# V-00716-02.net
KiCad netlist of a schematic drawn in EAGLE
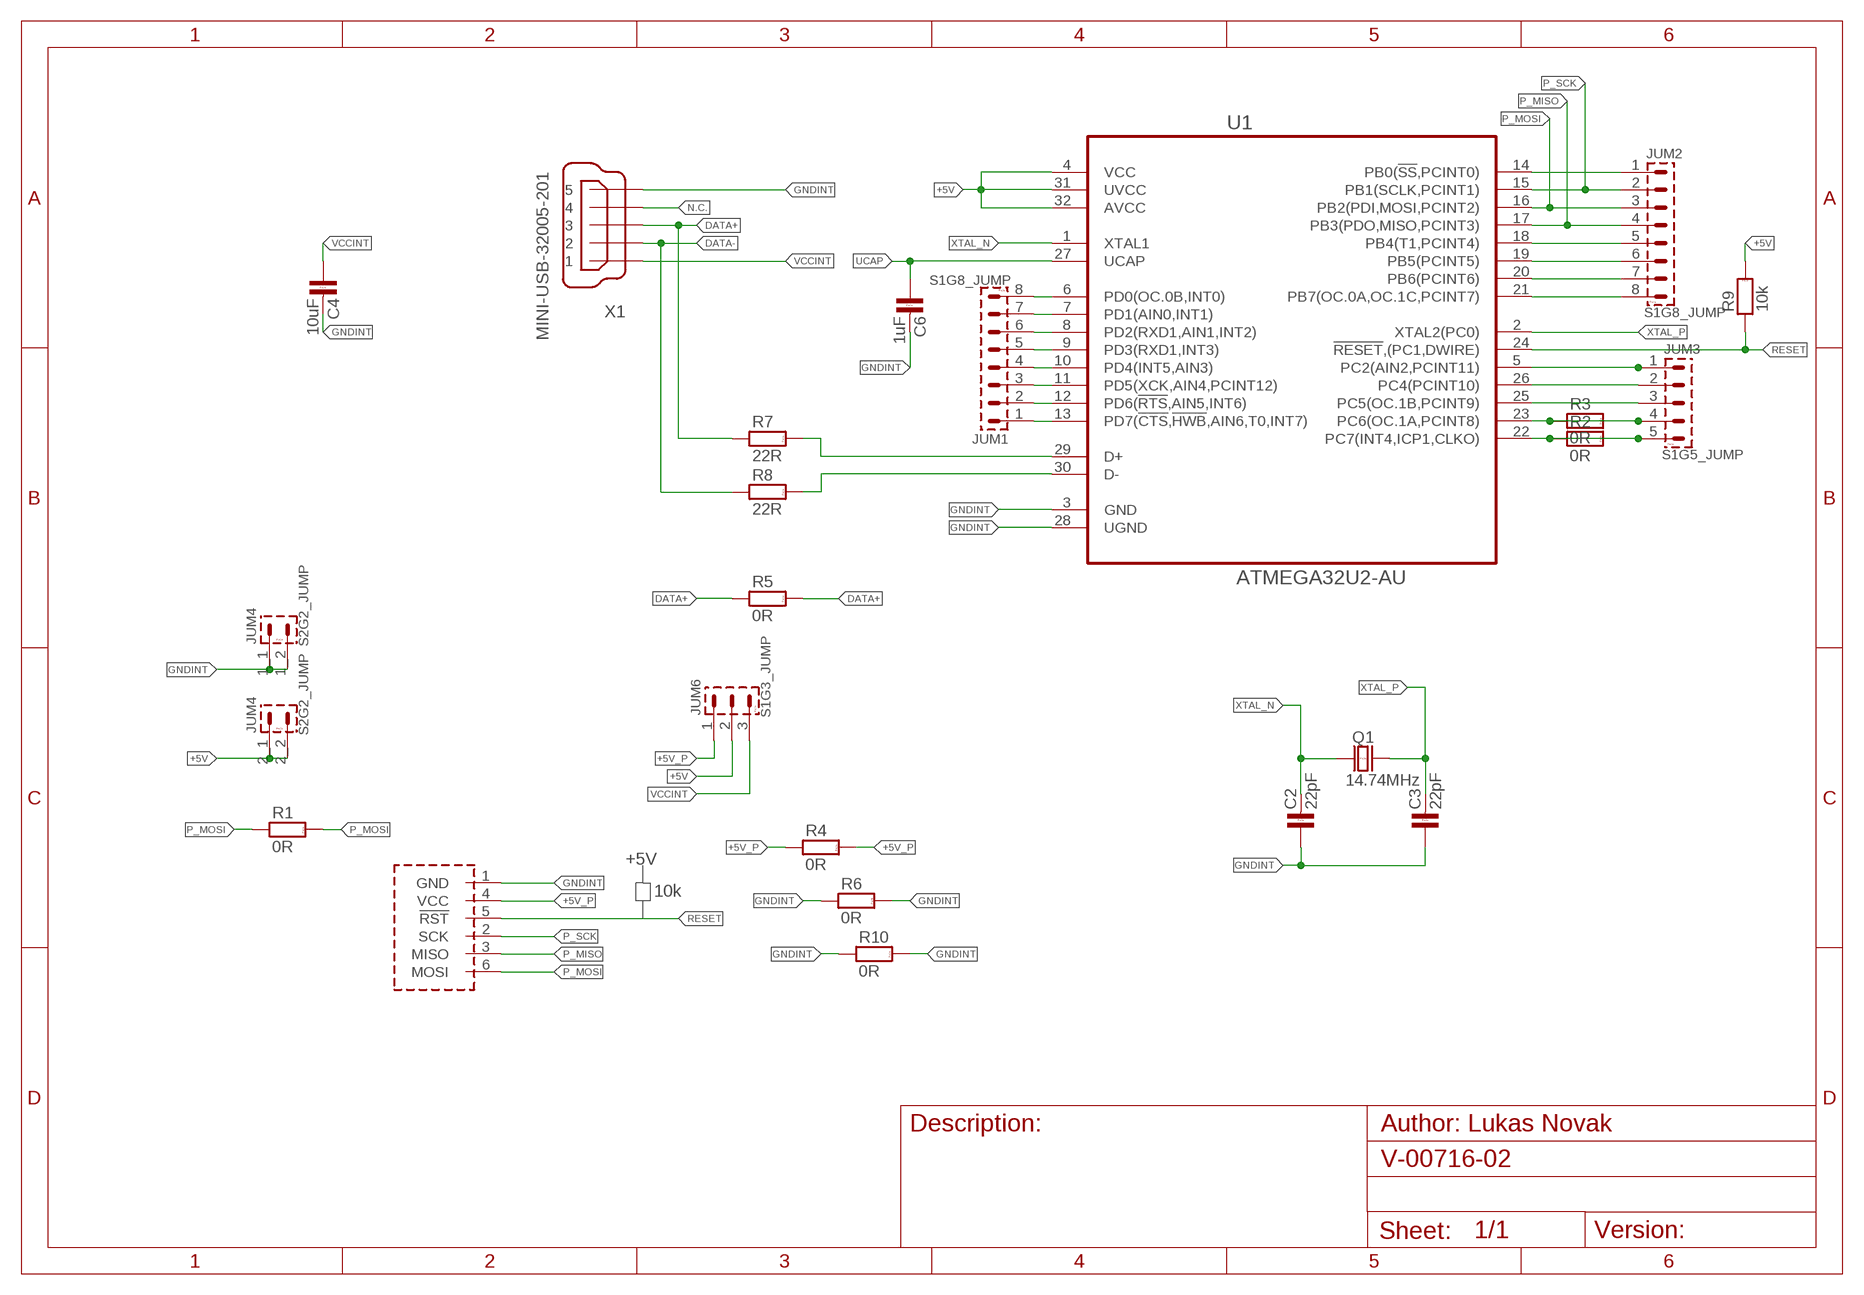
[diagram p0: schematic, sheet 1]

(export (version "E")
  (design (tool "Eeschema 10.0.6"))
  (components
    (comp (ref "C2")
      (value "22pF")
      (footprint "eagle-import:0805")
      (libsource (lib "eagle-import") (part "C-KER_0805"))
    )
    (comp (ref "C3")
      (value "22pF")
      (footprint "eagle-import:0805")
      (libsource (lib "eagle-import") (part "C-KER_0805"))
    )
    (comp (ref "C4")
      (value "10uF")
      (footprint "eagle-import:1206")
      (libsource (lib "eagle-import") (part "C-KER_1206"))
    )
    (comp (ref "C6")
      (value "1uF")
      (footprint "eagle-import:1206")
      (libsource (lib "eagle-import") (part "C-KER_1206"))
    )
    (comp (ref "JUM1")
      (value "S1G8_JUMP")
      (footprint "eagle-import:S1G8_JUM")
      (libsource (lib "eagle-import") (part "S1G8_JUMP"))
    )
    (comp (ref "JUM2")
      (value "S1G8_JUMP")
      (footprint "eagle-import:S1G8_JUM")
      (libsource (lib "eagle-import") (part "S1G8_JUMP"))
    )
    (comp (ref "JUM3")
      (value "S1G5_JUMP")
      (footprint "eagle-import:S1G5_JUM")
      (libsource (lib "eagle-import") (part "S1G5_JUMP"))
    )
    (comp (ref "JUM4")
      (value "S2G2_JUMP")
      (footprint "eagle-import:S2G2_JUM")
      (libsource (lib "eagle-import") (part "S2G2_JUMP"))
    )
    (comp (ref "JUM6")
      (value "S1G3_JUMP")
      (footprint "eagle-import:S1G3_JUM")
      (libsource (lib "eagle-import") (part "S1G3_JUMP"))
    )
    (comp (ref "Q1")
      (value "14.74MHz")
      (footprint "eagle-import:HC-49U")
      (libsource (lib "eagle-import") (part "Q_HC-49U"))
    )
    (comp (ref "R1")
      (value "0R")
      (footprint "eagle-import:1206")
      (libsource (lib "eagle-import") (part "R_1206"))
    )
    (comp (ref "R2")
      (value "0R")
      (footprint "eagle-import:1206")
      (libsource (lib "eagle-import") (part "R_1206"))
    )
    (comp (ref "R3")
      (value "0R")
      (footprint "eagle-import:1206")
      (libsource (lib "eagle-import") (part "R_1206"))
    )
    (comp (ref "R4")
      (value "0R")
      (footprint "eagle-import:1206")
      (libsource (lib "eagle-import") (part "R_1206"))
    )
    (comp (ref "R5")
      (value "0R")
      (footprint "eagle-import:1206")
      (libsource (lib "eagle-import") (part "R_1206"))
    )
    (comp (ref "R6")
      (value "0R")
      (footprint "eagle-import:1206")
      (libsource (lib "eagle-import") (part "R_1206"))
    )
    (comp (ref "R7")
      (value "22R")
      (footprint "eagle-import:1206")
      (libsource (lib "eagle-import") (part "R_1206"))
    )
    (comp (ref "R8")
      (value "22R")
      (footprint "eagle-import:1206")
      (libsource (lib "eagle-import") (part "R_1206"))
    )
    (comp (ref "R9")
      (value "10k")
      (footprint "eagle-import:1206")
      (libsource (lib "eagle-import") (part "R_1206"))
    )
    (comp (ref "R10")
      (value "0R")
      (footprint "eagle-import:1206")
      (libsource (lib "eagle-import") (part "R_1206"))
    )
    (comp (ref "U$1")
      (value "AVR_PROG_SPI")
      (footprint "eagle-import:PSH02-06P")
      (libsource (lib "eagle-import") (part "AVR_PROG_SPI"))
    )
    (comp (ref "U1")
      (value "ATMEGA32U2-AU")
      (footprint "eagle-import:QFP80P900X900X120-32N")
      (libsource (lib "eagle-import") (part "ATMEGA32U2-AU"))
    )
    (comp (ref "X1")
      (value "MINI-USB-32005-201")
      (footprint "eagle-import:32005-201")
      (libsource (lib "eagle-import") (part "MINI-USB-32005-201"))
    )
  )
  (nets
    (net (code "1") (name "+5V") (class "Default")
      (node (ref "JUM4") (pin "2_1") (pinfunction "1_2_1") (pintype "passive"))
      (node (ref "JUM4") (pin "2_2") (pinfunction "2_2_2") (pintype "passive"))
      (node (ref "JUM6") (pin "2") (pinfunction "2_2") (pintype "passive"))
      (node (ref "R9") (pin "2") (pinfunction "2_2") (pintype "passive"))
      (node (ref "U1") (pin "31") (pinfunction "UVCC_31") (pintype "power_in"))
      (node (ref "U1") (pin "32") (pinfunction "AVCC_32") (pintype "power_in"))
      (node (ref "U1") (pin "4") (pinfunction "VCC_4") (pintype "power_in"))
    )
    (net (code "2") (name "+5V_P") (class "Default")
      (node (ref "JUM6") (pin "1") (pinfunction "1_1") (pintype "passive"))
      (node (ref "R4") (pin "1") (pinfunction "1_1") (pintype "passive"))
      (node (ref "R4") (pin "2") (pinfunction "2_2") (pintype "passive"))
      (node (ref "U$1") (pin "4") (pinfunction "VCC_4") (pintype "bidirectional"))
    )
    (net (code "3") (name "DATA+") (class "Default")
      (node (ref "R5") (pin "1") (pinfunction "1_1") (pintype "passive"))
      (node (ref "R5") (pin "2") (pinfunction "2_2") (pintype "passive"))
      (node (ref "R7") (pin "1") (pinfunction "1_1") (pintype "passive"))
      (node (ref "X1") (pin "3") (pinfunction "3_3") (pintype "passive"))
    )
    (net (code "4") (name "DATA-") (class "Default")
      (node (ref "R8") (pin "1") (pinfunction "1_1") (pintype "passive"))
      (node (ref "X1") (pin "2") (pinfunction "2_2") (pintype "passive"))
    )
    (net (code "5") (name "GNDINT") (class "Default")
      (node (ref "C2") (pin "1") (pinfunction "1_1") (pintype "passive"))
      (node (ref "C3") (pin "1") (pinfunction "1_1") (pintype "passive"))
      (node (ref "C4") (pin "2") (pinfunction "2_2") (pintype "passive"))
      (node (ref "C6") (pin "2") (pinfunction "2_2") (pintype "passive"))
      (node (ref "JUM4") (pin "1_1") (pinfunction "1_1_1") (pintype "passive"))
      (node (ref "JUM4") (pin "1_2") (pinfunction "2_1_2") (pintype "passive"))
      (node (ref "R10") (pin "1") (pinfunction "1_1") (pintype "passive"))
      (node (ref "R10") (pin "2") (pinfunction "2_2") (pintype "passive"))
      (node (ref "R6") (pin "1") (pinfunction "1_1") (pintype "passive"))
      (node (ref "R6") (pin "2") (pinfunction "2_2") (pintype "passive"))
      (node (ref "U$1") (pin "1") (pinfunction "GND_1") (pintype "bidirectional"))
      (node (ref "U1") (pin "28") (pinfunction "UGND_28") (pintype "passive"))
      (node (ref "U1") (pin "3") (pinfunction "GND_3") (pintype "passive"))
      (node (ref "X1") (pin "5") (pinfunction "5_5") (pintype "passive"))
    )
    (net (code "6") (name "N.C.") (class "Default")
      (node (ref "X1") (pin "4") (pinfunction "4_4") (pintype "passive"))
    )
    (net (code "7") (name "Net-(U1-D+)") (class "Default")
      (node (ref "R7") (pin "2") (pinfunction "2_2") (pintype "passive"))
      (node (ref "U1") (pin "29") (pinfunction "D+_29") (pintype "bidirectional"))
    )
    (net (code "8") (name "Net-(U1-D-)") (class "Default")
      (node (ref "R8") (pin "2") (pinfunction "2_2") (pintype "passive"))
      (node (ref "U1") (pin "30") (pinfunction "D-_30") (pintype "bidirectional"))
    )
    (net (code "9") (name "Net-(U1-PB0(~{SS,PCINT0}))") (class "Default")
      (node (ref "JUM2") (pin "1") (pinfunction "1_1") (pintype "passive"))
      (node (ref "U1") (pin "14") (pinfunction "PB0(~{SS,PCINT0})_14") (pintype "bidirectional"))
    )
    (net (code "10") (name "Net-(U1-PB4(T1,PCINT4))") (class "Default")
      (node (ref "JUM2") (pin "5") (pinfunction "5_5") (pintype "passive"))
      (node (ref "U1") (pin "18") (pinfunction "PB4(T1,PCINT4)_18") (pintype "bidirectional"))
    )
    (net (code "11") (name "Net-(U1-PB5(PCINT5))") (class "Default")
      (node (ref "JUM2") (pin "6") (pinfunction "6_6") (pintype "passive"))
      (node (ref "U1") (pin "19") (pinfunction "PB5(PCINT5)_19") (pintype "bidirectional"))
    )
    (net (code "12") (name "Net-(U1-PB6(PCINT6))") (class "Default")
      (node (ref "JUM2") (pin "7") (pinfunction "7_7") (pintype "passive"))
      (node (ref "U1") (pin "20") (pinfunction "PB6(PCINT6)_20") (pintype "bidirectional"))
    )
    (net (code "13") (name "Net-(U1-PB7(OC.0A,OC.1C,PCINT7))") (class "Default")
      (node (ref "JUM2") (pin "8") (pinfunction "8_8") (pintype "passive"))
      (node (ref "U1") (pin "21") (pinfunction "PB7(OC.0A,OC.1C,PCINT7)_21") (pintype "bidirectional"))
    )
    (net (code "14") (name "Net-(U1-PC2(AIN2,PCINT11))") (class "Default")
      (node (ref "JUM3") (pin "1") (pinfunction "1_1") (pintype "passive"))
      (node (ref "U1") (pin "5") (pinfunction "PC2(AIN2,PCINT11)_5") (pintype "bidirectional"))
    )
    (net (code "15") (name "Net-(U1-PC4(PCINT10))") (class "Default")
      (node (ref "JUM3") (pin "2") (pinfunction "2_2") (pintype "passive"))
      (node (ref "U1") (pin "26") (pinfunction "PC4(PCINT10)_26") (pintype "bidirectional"))
    )
    (net (code "16") (name "Net-(U1-PC5(OC.1B,PCINT9))") (class "Default")
      (node (ref "JUM3") (pin "3") (pinfunction "3_3") (pintype "passive"))
      (node (ref "U1") (pin "25") (pinfunction "PC5(OC.1B,PCINT9)_25") (pintype "bidirectional"))
    )
    (net (code "17") (name "Net-(U1-PC6(OC.1A,PCINT8))") (class "Default")
      (node (ref "JUM3") (pin "4") (pinfunction "4_4") (pintype "passive"))
      (node (ref "R3") (pin "1") (pinfunction "1_1") (pintype "passive"))
      (node (ref "R3") (pin "2") (pinfunction "2_2") (pintype "passive"))
      (node (ref "U1") (pin "23") (pinfunction "PC6(OC.1A,PCINT8)_23") (pintype "bidirectional"))
    )
    (net (code "18") (name "Net-(U1-PC7(INT4,ICP1,CLKO))") (class "Default")
      (node (ref "JUM3") (pin "5") (pinfunction "5_5") (pintype "passive"))
      (node (ref "R2") (pin "1") (pinfunction "1_1") (pintype "passive"))
      (node (ref "R2") (pin "2") (pinfunction "2_2") (pintype "passive"))
      (node (ref "U1") (pin "22") (pinfunction "PC7(INT4,ICP1,CLKO)_22") (pintype "bidirectional"))
    )
    (net (code "19") (name "Net-(U1-PD0(OC.0B,INT0))") (class "Default")
      (node (ref "JUM1") (pin "8") (pinfunction "8_8") (pintype "passive"))
      (node (ref "U1") (pin "6") (pinfunction "PD0(OC.0B,INT0)_6") (pintype "bidirectional"))
    )
    (net (code "20") (name "Net-(U1-PD1(AIN0,INT1))") (class "Default")
      (node (ref "JUM1") (pin "7") (pinfunction "7_7") (pintype "passive"))
      (node (ref "U1") (pin "7") (pinfunction "PD1(AIN0,INT1)_7") (pintype "bidirectional"))
    )
    (net (code "21") (name "Net-(U1-PD2(RXD1,AIN1,INT2))") (class "Default")
      (node (ref "JUM1") (pin "6") (pinfunction "6_6") (pintype "passive"))
      (node (ref "U1") (pin "8") (pinfunction "PD2(RXD1,AIN1,INT2)_8") (pintype "bidirectional"))
    )
    (net (code "22") (name "Net-(U1-PD3(RXD1,INT3))") (class "Default")
      (node (ref "JUM1") (pin "5") (pinfunction "5_5") (pintype "passive"))
      (node (ref "U1") (pin "9") (pinfunction "PD3(RXD1,INT3)_9") (pintype "bidirectional"))
    )
    (net (code "23") (name "Net-(U1-PD4(INT5,AIN3))") (class "Default")
      (node (ref "JUM1") (pin "4") (pinfunction "4_4") (pintype "passive"))
      (node (ref "U1") (pin "10") (pinfunction "PD4(INT5,AIN3)_10") (pintype "bidirectional"))
    )
    (net (code "24") (name "Net-(U1-PD5(XCK,AIN4,PCINT12))") (class "Default")
      (node (ref "JUM1") (pin "3") (pinfunction "3_3") (pintype "passive"))
      (node (ref "U1") (pin "11") (pinfunction "PD5(XCK,AIN4,PCINT12)_11") (pintype "bidirectional"))
    )
    (net (code "25") (name "Net-(U1-PD6(~{RTS,AIN5,INT6}))") (class "Default")
      (node (ref "JUM1") (pin "2") (pinfunction "2_2") (pintype "passive"))
      (node (ref "U1") (pin "12") (pinfunction "PD6(~{RTS,AIN5,INT6})_12") (pintype "bidirectional"))
    )
    (net (code "26") (name "Net-(U1-PD7(~{CTS,}HWB,AIN6,T0,INT7))") (class "Default")
      (node (ref "JUM1") (pin "1") (pinfunction "1_1") (pintype "passive"))
      (node (ref "U1") (pin "13") (pinfunction "PD7(~{CTS,}HWB,AIN6,T0,INT7)_13") (pintype "bidirectional"))
    )
    (net (code "27") (name "P_MISO") (class "Default")
      (node (ref "JUM2") (pin "4") (pinfunction "4_4") (pintype "passive"))
      (node (ref "U$1") (pin "3") (pinfunction "MISO_3") (pintype "bidirectional"))
      (node (ref "U1") (pin "17") (pinfunction "PB3(PDO,MISO,PCINT3)_17") (pintype "bidirectional"))
    )
    (net (code "28") (name "P_MOSI") (class "Default")
      (node (ref "JUM2") (pin "3") (pinfunction "3_3") (pintype "passive"))
      (node (ref "R1") (pin "1") (pinfunction "1_1") (pintype "passive"))
      (node (ref "R1") (pin "2") (pinfunction "2_2") (pintype "passive"))
      (node (ref "U$1") (pin "6") (pinfunction "MOSI_6") (pintype "bidirectional"))
      (node (ref "U1") (pin "16") (pinfunction "PB2(PDI,MOSI,PCINT2)_16") (pintype "bidirectional"))
    )
    (net (code "29") (name "P_SCK") (class "Default")
      (node (ref "JUM2") (pin "2") (pinfunction "2_2") (pintype "passive"))
      (node (ref "U$1") (pin "2") (pinfunction "SCK_2") (pintype "bidirectional"))
      (node (ref "U1") (pin "15") (pinfunction "PB1(SCLK,PCINT1)_15") (pintype "bidirectional"))
    )
    (net (code "30") (name "RESET") (class "Default")
      (node (ref "R9") (pin "1") (pinfunction "1_1") (pintype "passive"))
      (node (ref "U$1") (pin "5") (pinfunction "~{RST}_5") (pintype "bidirectional"))
      (node (ref "U1") (pin "24") (pinfunction "~{RESET,(PC1,DWIRE})_24") (pintype "bidirectional"))
    )
    (net (code "31") (name "UCAP") (class "Default")
      (node (ref "C6") (pin "1") (pinfunction "1_1") (pintype "passive"))
      (node (ref "U1") (pin "27") (pinfunction "UCAP_27") (pintype "power_in"))
    )
    (net (code "32") (name "VCCINT") (class "Default")
      (node (ref "C4") (pin "1") (pinfunction "1_1") (pintype "passive"))
      (node (ref "JUM6") (pin "3") (pinfunction "3_3") (pintype "passive"))
      (node (ref "X1") (pin "1") (pinfunction "1_1") (pintype "passive"))
    )
    (net (code "33") (name "XTAL_N") (class "Default")
      (node (ref "C2") (pin "2") (pinfunction "2_2") (pintype "passive"))
      (node (ref "Q1") (pin "1") (pinfunction "1_1") (pintype "passive"))
      (node (ref "U1") (pin "1") (pinfunction "XTAL1_1") (pintype "input"))
    )
    (net (code "34") (name "XTAL_P") (class "Default")
      (node (ref "C3") (pin "2") (pinfunction "2_2") (pintype "passive"))
      (node (ref "Q1") (pin "2") (pinfunction "2_2") (pintype "passive"))
      (node (ref "U1") (pin "2") (pinfunction "XTAL2(PC0)_2") (pintype "bidirectional"))
    )
  )
)
